# source_eagle.net
KiCad netlist of a schematic drawn in EAGLE
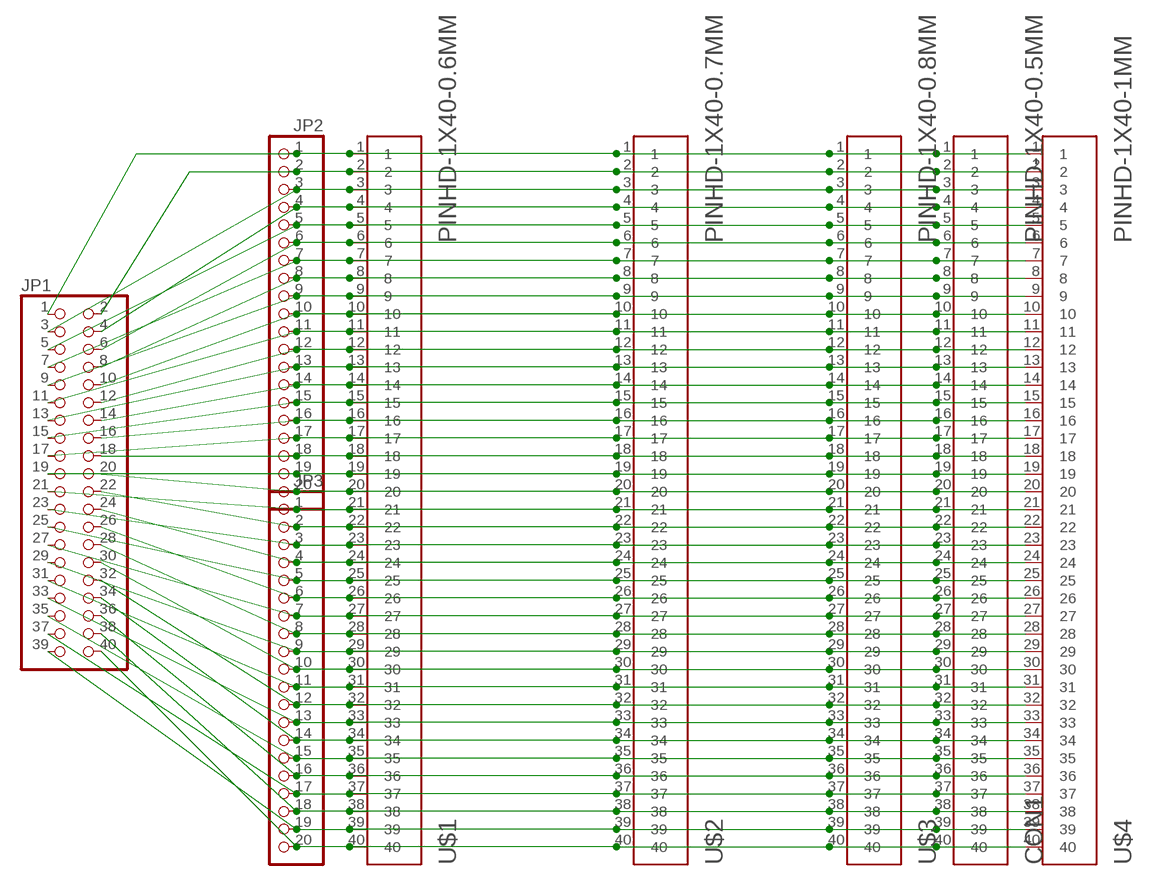
[diagram p0: schematic, sheet 1]

(export (version "E")
  (design (tool "Eeschema 10.0.6"))
  (components
    (comp (ref "CON1")
      (value "PINHD-1X40-0.5MM")
      (footprint "eagle-import:1X40-0.5MM")
      (libsource (lib "eagle-import") (part "PINHD-1X40-0.5MM"))
    )
    (comp (ref "JP1")
      (value "PINHD-2X20-BIG")
      (footprint "eagle-import:2X20-BIG")
      (libsource (lib "eagle-import") (part "PINHD-2X20-BIG"))
    )
    (comp (ref "JP2")
      (value "PINHD-1X20-BIG")
      (footprint "eagle-import:1X20-BIG")
      (libsource (lib "eagle-import") (part "PINHD-1X20-BIG"))
    )
    (comp (ref "JP3")
      (value "PINHD-1X20-BIG")
      (footprint "eagle-import:1X20-BIG")
      (libsource (lib "eagle-import") (part "PINHD-1X20-BIG"))
    )
    (comp (ref "U$1")
      (value "PINHD-1X40-0.6MM")
      (footprint "eagle-import:1X40-0.6MM")
      (libsource (lib "eagle-import") (part "PINHD-1X40-0.6MM"))
    )
    (comp (ref "U$2")
      (value "PINHD-1X40-0.7MM")
      (footprint "eagle-import:1X40-0.7MM")
      (libsource (lib "eagle-import") (part "PINHD-1X40-0.7MM"))
    )
    (comp (ref "U$3")
      (value "PINHD-1X40-0.8MM")
      (footprint "eagle-import:1X40-0.8MM")
      (libsource (lib "eagle-import") (part "PINHD-1X40-0.8MM"))
    )
    (comp (ref "U$4")
      (value "PINHD-1X40-1MM")
      (footprint "eagle-import:1X40-1MM")
      (libsource (lib "eagle-import") (part "PINHD-1X40-1MM"))
    )
  )
  (nets
    (net (code "1") (name "Net-(CON1-Pad1)") (class "Default")
      (node (ref "CON1") (pin "1") (pinfunction "1_1") (pintype "bidirectional"))
      (node (ref "JP1") (pin "1") (pinfunction "1_1") (pintype "passive"))
      (node (ref "JP2") (pin "1") (pinfunction "1_1") (pintype "passive"))
      (node (ref "U$1") (pin "1") (pinfunction "1_1") (pintype "bidirectional"))
      (node (ref "U$2") (pin "1") (pinfunction "1_1") (pintype "bidirectional"))
      (node (ref "U$3") (pin "1") (pinfunction "1_1") (pintype "bidirectional"))
      (node (ref "U$4") (pin "1") (pinfunction "1_1") (pintype "bidirectional"))
    )
    (net (code "2") (name "Net-(CON1-Pad2)") (class "Default")
      (node (ref "CON1") (pin "2") (pinfunction "2_2") (pintype "bidirectional"))
      (node (ref "JP1") (pin "2") (pinfunction "2_2") (pintype "passive"))
      (node (ref "JP2") (pin "2") (pinfunction "2_2") (pintype "passive"))
      (node (ref "U$1") (pin "2") (pinfunction "2_2") (pintype "bidirectional"))
      (node (ref "U$2") (pin "2") (pinfunction "2_2") (pintype "bidirectional"))
      (node (ref "U$3") (pin "2") (pinfunction "2_2") (pintype "bidirectional"))
      (node (ref "U$4") (pin "2") (pinfunction "2_2") (pintype "bidirectional"))
    )
    (net (code "3") (name "Net-(CON1-Pad3)") (class "Default")
      (node (ref "CON1") (pin "3") (pinfunction "3_3") (pintype "bidirectional"))
      (node (ref "JP1") (pin "3") (pinfunction "3_3") (pintype "passive"))
      (node (ref "JP2") (pin "3") (pinfunction "3_3") (pintype "passive"))
      (node (ref "U$1") (pin "3") (pinfunction "3_3") (pintype "bidirectional"))
      (node (ref "U$2") (pin "3") (pinfunction "3_3") (pintype "bidirectional"))
      (node (ref "U$3") (pin "3") (pinfunction "3_3") (pintype "bidirectional"))
      (node (ref "U$4") (pin "3") (pinfunction "3_3") (pintype "bidirectional"))
    )
    (net (code "4") (name "Net-(CON1-Pad4)") (class "Default")
      (node (ref "CON1") (pin "4") (pinfunction "4_4") (pintype "bidirectional"))
      (node (ref "JP1") (pin "4") (pinfunction "4_4") (pintype "passive"))
      (node (ref "JP2") (pin "4") (pinfunction "4_4") (pintype "passive"))
      (node (ref "U$1") (pin "4") (pinfunction "4_4") (pintype "bidirectional"))
      (node (ref "U$2") (pin "4") (pinfunction "4_4") (pintype "bidirectional"))
      (node (ref "U$3") (pin "4") (pinfunction "4_4") (pintype "bidirectional"))
      (node (ref "U$4") (pin "4") (pinfunction "4_4") (pintype "bidirectional"))
    )
    (net (code "5") (name "Net-(CON1-Pad5)") (class "Default")
      (node (ref "CON1") (pin "5") (pinfunction "5_5") (pintype "bidirectional"))
      (node (ref "JP1") (pin "5") (pinfunction "5_5") (pintype "passive"))
      (node (ref "JP2") (pin "5") (pinfunction "5_5") (pintype "passive"))
      (node (ref "U$1") (pin "5") (pinfunction "5_5") (pintype "bidirectional"))
      (node (ref "U$2") (pin "5") (pinfunction "5_5") (pintype "bidirectional"))
      (node (ref "U$3") (pin "5") (pinfunction "5_5") (pintype "bidirectional"))
      (node (ref "U$4") (pin "5") (pinfunction "5_5") (pintype "bidirectional"))
    )
    (net (code "6") (name "Net-(CON1-Pad6)") (class "Default")
      (node (ref "CON1") (pin "6") (pinfunction "6_6") (pintype "bidirectional"))
      (node (ref "JP1") (pin "6") (pinfunction "6_6") (pintype "passive"))
      (node (ref "JP2") (pin "6") (pinfunction "6_6") (pintype "passive"))
      (node (ref "U$1") (pin "6") (pinfunction "6_6") (pintype "bidirectional"))
      (node (ref "U$2") (pin "6") (pinfunction "6_6") (pintype "bidirectional"))
      (node (ref "U$3") (pin "6") (pinfunction "6_6") (pintype "bidirectional"))
      (node (ref "U$4") (pin "6") (pinfunction "6_6") (pintype "bidirectional"))
    )
    (net (code "7") (name "Net-(CON1-Pad7)") (class "Default")
      (node (ref "CON1") (pin "7") (pinfunction "7_7") (pintype "bidirectional"))
      (node (ref "JP1") (pin "7") (pinfunction "7_7") (pintype "passive"))
      (node (ref "JP2") (pin "7") (pinfunction "7_7") (pintype "passive"))
      (node (ref "U$1") (pin "7") (pinfunction "7_7") (pintype "bidirectional"))
      (node (ref "U$2") (pin "7") (pinfunction "7_7") (pintype "bidirectional"))
      (node (ref "U$3") (pin "7") (pinfunction "7_7") (pintype "bidirectional"))
      (node (ref "U$4") (pin "7") (pinfunction "7_7") (pintype "bidirectional"))
    )
    (net (code "8") (name "Net-(CON1-Pad8)") (class "Default")
      (node (ref "CON1") (pin "8") (pinfunction "8_8") (pintype "bidirectional"))
      (node (ref "JP1") (pin "8") (pinfunction "8_8") (pintype "passive"))
      (node (ref "JP2") (pin "8") (pinfunction "8_8") (pintype "passive"))
      (node (ref "U$1") (pin "8") (pinfunction "8_8") (pintype "bidirectional"))
      (node (ref "U$2") (pin "8") (pinfunction "8_8") (pintype "bidirectional"))
      (node (ref "U$3") (pin "8") (pinfunction "8_8") (pintype "bidirectional"))
      (node (ref "U$4") (pin "8") (pinfunction "8_8") (pintype "bidirectional"))
    )
    (net (code "9") (name "Net-(CON1-Pad9)") (class "Default")
      (node (ref "CON1") (pin "9") (pinfunction "9_9") (pintype "bidirectional"))
      (node (ref "JP1") (pin "9") (pinfunction "9_9") (pintype "passive"))
      (node (ref "JP2") (pin "9") (pinfunction "9_9") (pintype "passive"))
      (node (ref "U$1") (pin "9") (pinfunction "9_9") (pintype "bidirectional"))
      (node (ref "U$2") (pin "9") (pinfunction "9_9") (pintype "bidirectional"))
      (node (ref "U$3") (pin "9") (pinfunction "9_9") (pintype "bidirectional"))
      (node (ref "U$4") (pin "9") (pinfunction "9_9") (pintype "bidirectional"))
    )
    (net (code "10") (name "Net-(CON1-Pad10)") (class "Default")
      (node (ref "CON1") (pin "10") (pinfunction "10_10") (pintype "bidirectional"))
      (node (ref "JP1") (pin "10") (pinfunction "10_10") (pintype "passive"))
      (node (ref "JP2") (pin "10") (pinfunction "10_10") (pintype "passive"))
      (node (ref "U$1") (pin "10") (pinfunction "10_10") (pintype "bidirectional"))
      (node (ref "U$2") (pin "10") (pinfunction "10_10") (pintype "bidirectional"))
      (node (ref "U$3") (pin "10") (pinfunction "10_10") (pintype "bidirectional"))
      (node (ref "U$4") (pin "10") (pinfunction "10_10") (pintype "bidirectional"))
    )
    (net (code "11") (name "Net-(CON1-Pad11)") (class "Default")
      (node (ref "CON1") (pin "11") (pinfunction "11_11") (pintype "bidirectional"))
      (node (ref "JP1") (pin "11") (pinfunction "11_11") (pintype "passive"))
      (node (ref "JP2") (pin "11") (pinfunction "11_11") (pintype "passive"))
      (node (ref "U$1") (pin "11") (pinfunction "11_11") (pintype "bidirectional"))
      (node (ref "U$2") (pin "11") (pinfunction "11_11") (pintype "bidirectional"))
      (node (ref "U$3") (pin "11") (pinfunction "11_11") (pintype "bidirectional"))
      (node (ref "U$4") (pin "11") (pinfunction "11_11") (pintype "bidirectional"))
    )
    (net (code "12") (name "Net-(CON1-Pad12)") (class "Default")
      (node (ref "CON1") (pin "12") (pinfunction "12_12") (pintype "bidirectional"))
      (node (ref "JP1") (pin "12") (pinfunction "12_12") (pintype "passive"))
      (node (ref "JP2") (pin "12") (pinfunction "12_12") (pintype "passive"))
      (node (ref "U$1") (pin "12") (pinfunction "12_12") (pintype "bidirectional"))
      (node (ref "U$2") (pin "12") (pinfunction "12_12") (pintype "bidirectional"))
      (node (ref "U$3") (pin "12") (pinfunction "12_12") (pintype "bidirectional"))
      (node (ref "U$4") (pin "12") (pinfunction "12_12") (pintype "bidirectional"))
    )
    (net (code "13") (name "Net-(CON1-Pad13)") (class "Default")
      (node (ref "CON1") (pin "13") (pinfunction "13_13") (pintype "bidirectional"))
      (node (ref "JP1") (pin "13") (pinfunction "13_13") (pintype "passive"))
      (node (ref "JP2") (pin "13") (pinfunction "13_13") (pintype "passive"))
      (node (ref "U$1") (pin "13") (pinfunction "13_13") (pintype "bidirectional"))
      (node (ref "U$2") (pin "13") (pinfunction "13_13") (pintype "bidirectional"))
      (node (ref "U$3") (pin "13") (pinfunction "13_13") (pintype "bidirectional"))
      (node (ref "U$4") (pin "13") (pinfunction "13_13") (pintype "bidirectional"))
    )
    (net (code "14") (name "Net-(CON1-Pad14)") (class "Default")
      (node (ref "CON1") (pin "14") (pinfunction "14_14") (pintype "bidirectional"))
      (node (ref "JP1") (pin "14") (pinfunction "14_14") (pintype "passive"))
      (node (ref "JP2") (pin "14") (pinfunction "14_14") (pintype "passive"))
      (node (ref "U$1") (pin "14") (pinfunction "14_14") (pintype "bidirectional"))
      (node (ref "U$2") (pin "14") (pinfunction "14_14") (pintype "bidirectional"))
      (node (ref "U$3") (pin "14") (pinfunction "14_14") (pintype "bidirectional"))
      (node (ref "U$4") (pin "14") (pinfunction "14_14") (pintype "bidirectional"))
    )
    (net (code "15") (name "Net-(CON1-Pad15)") (class "Default")
      (node (ref "CON1") (pin "15") (pinfunction "15_15") (pintype "bidirectional"))
      (node (ref "JP1") (pin "15") (pinfunction "15_15") (pintype "passive"))
      (node (ref "JP2") (pin "15") (pinfunction "15_15") (pintype "passive"))
      (node (ref "U$1") (pin "15") (pinfunction "15_15") (pintype "bidirectional"))
      (node (ref "U$2") (pin "15") (pinfunction "15_15") (pintype "bidirectional"))
      (node (ref "U$3") (pin "15") (pinfunction "15_15") (pintype "bidirectional"))
      (node (ref "U$4") (pin "15") (pinfunction "15_15") (pintype "bidirectional"))
    )
    (net (code "16") (name "Net-(CON1-Pad16)") (class "Default")
      (node (ref "CON1") (pin "16") (pinfunction "16_16") (pintype "bidirectional"))
      (node (ref "JP1") (pin "16") (pinfunction "16_16") (pintype "passive"))
      (node (ref "JP2") (pin "16") (pinfunction "16_16") (pintype "passive"))
      (node (ref "U$1") (pin "16") (pinfunction "16_16") (pintype "bidirectional"))
      (node (ref "U$2") (pin "16") (pinfunction "16_16") (pintype "bidirectional"))
      (node (ref "U$3") (pin "16") (pinfunction "16_16") (pintype "bidirectional"))
      (node (ref "U$4") (pin "16") (pinfunction "16_16") (pintype "bidirectional"))
    )
    (net (code "17") (name "Net-(CON1-Pad17)") (class "Default")
      (node (ref "CON1") (pin "17") (pinfunction "17_17") (pintype "bidirectional"))
      (node (ref "JP1") (pin "17") (pinfunction "17_17") (pintype "passive"))
      (node (ref "JP2") (pin "17") (pinfunction "17_17") (pintype "passive"))
      (node (ref "U$1") (pin "17") (pinfunction "17_17") (pintype "bidirectional"))
      (node (ref "U$2") (pin "17") (pinfunction "17_17") (pintype "bidirectional"))
      (node (ref "U$3") (pin "17") (pinfunction "17_17") (pintype "bidirectional"))
      (node (ref "U$4") (pin "17") (pinfunction "17_17") (pintype "bidirectional"))
    )
    (net (code "18") (name "Net-(CON1-Pad18)") (class "Default")
      (node (ref "CON1") (pin "18") (pinfunction "18_18") (pintype "bidirectional"))
      (node (ref "JP1") (pin "18") (pinfunction "18_18") (pintype "passive"))
      (node (ref "JP2") (pin "18") (pinfunction "18_18") (pintype "passive"))
      (node (ref "U$1") (pin "18") (pinfunction "18_18") (pintype "bidirectional"))
      (node (ref "U$2") (pin "18") (pinfunction "18_18") (pintype "bidirectional"))
      (node (ref "U$3") (pin "18") (pinfunction "18_18") (pintype "bidirectional"))
      (node (ref "U$4") (pin "18") (pinfunction "18_18") (pintype "bidirectional"))
    )
    (net (code "19") (name "Net-(CON1-Pad19)") (class "Default")
      (node (ref "CON1") (pin "19") (pinfunction "19_19") (pintype "bidirectional"))
      (node (ref "JP1") (pin "19") (pinfunction "19_19") (pintype "passive"))
      (node (ref "JP2") (pin "19") (pinfunction "19_19") (pintype "passive"))
      (node (ref "U$1") (pin "19") (pinfunction "19_19") (pintype "bidirectional"))
      (node (ref "U$2") (pin "19") (pinfunction "19_19") (pintype "bidirectional"))
      (node (ref "U$3") (pin "19") (pinfunction "19_19") (pintype "bidirectional"))
      (node (ref "U$4") (pin "19") (pinfunction "19_19") (pintype "bidirectional"))
    )
    (net (code "20") (name "Net-(CON1-Pad20)") (class "Default")
      (node (ref "CON1") (pin "20") (pinfunction "20_20") (pintype "bidirectional"))
      (node (ref "JP1") (pin "20") (pinfunction "20_20") (pintype "passive"))
      (node (ref "JP2") (pin "20") (pinfunction "20_20") (pintype "passive"))
      (node (ref "U$1") (pin "20") (pinfunction "20_20") (pintype "bidirectional"))
      (node (ref "U$2") (pin "20") (pinfunction "20_20") (pintype "bidirectional"))
      (node (ref "U$3") (pin "20") (pinfunction "20_20") (pintype "bidirectional"))
      (node (ref "U$4") (pin "20") (pinfunction "20_20") (pintype "bidirectional"))
    )
    (net (code "21") (name "Net-(CON1-Pad21)") (class "Default")
      (node (ref "CON1") (pin "21") (pinfunction "21_21") (pintype "bidirectional"))
      (node (ref "JP1") (pin "21") (pinfunction "21_21") (pintype "passive"))
      (node (ref "JP3") (pin "1") (pinfunction "1_1") (pintype "passive"))
      (node (ref "U$1") (pin "21") (pinfunction "21_21") (pintype "bidirectional"))
      (node (ref "U$2") (pin "21") (pinfunction "21_21") (pintype "bidirectional"))
      (node (ref "U$3") (pin "21") (pinfunction "21_21") (pintype "bidirectional"))
      (node (ref "U$4") (pin "21") (pinfunction "21_21") (pintype "bidirectional"))
    )
    (net (code "22") (name "Net-(CON1-Pad22)") (class "Default")
      (node (ref "CON1") (pin "22") (pinfunction "22_22") (pintype "bidirectional"))
      (node (ref "JP1") (pin "22") (pinfunction "22_22") (pintype "passive"))
      (node (ref "JP3") (pin "2") (pinfunction "2_2") (pintype "passive"))
      (node (ref "U$1") (pin "22") (pinfunction "22_22") (pintype "bidirectional"))
      (node (ref "U$2") (pin "22") (pinfunction "22_22") (pintype "bidirectional"))
      (node (ref "U$3") (pin "22") (pinfunction "22_22") (pintype "bidirectional"))
      (node (ref "U$4") (pin "22") (pinfunction "22_22") (pintype "bidirectional"))
    )
    (net (code "23") (name "Net-(CON1-Pad23)") (class "Default")
      (node (ref "CON1") (pin "23") (pinfunction "23_23") (pintype "bidirectional"))
      (node (ref "JP1") (pin "23") (pinfunction "23_23") (pintype "passive"))
      (node (ref "JP3") (pin "3") (pinfunction "3_3") (pintype "passive"))
      (node (ref "U$1") (pin "23") (pinfunction "23_23") (pintype "bidirectional"))
      (node (ref "U$2") (pin "23") (pinfunction "23_23") (pintype "bidirectional"))
      (node (ref "U$3") (pin "23") (pinfunction "23_23") (pintype "bidirectional"))
      (node (ref "U$4") (pin "23") (pinfunction "23_23") (pintype "bidirectional"))
    )
    (net (code "24") (name "Net-(CON1-Pad24)") (class "Default")
      (node (ref "CON1") (pin "24") (pinfunction "24_24") (pintype "bidirectional"))
      (node (ref "JP1") (pin "24") (pinfunction "24_24") (pintype "passive"))
      (node (ref "JP3") (pin "4") (pinfunction "4_4") (pintype "passive"))
      (node (ref "U$1") (pin "24") (pinfunction "24_24") (pintype "bidirectional"))
      (node (ref "U$2") (pin "24") (pinfunction "24_24") (pintype "bidirectional"))
      (node (ref "U$3") (pin "24") (pinfunction "24_24") (pintype "bidirectional"))
      (node (ref "U$4") (pin "24") (pinfunction "24_24") (pintype "bidirectional"))
    )
    (net (code "25") (name "Net-(CON1-Pad25)") (class "Default")
      (node (ref "CON1") (pin "25") (pinfunction "25_25") (pintype "bidirectional"))
      (node (ref "JP1") (pin "25") (pinfunction "25_25") (pintype "passive"))
      (node (ref "JP3") (pin "5") (pinfunction "5_5") (pintype "passive"))
      (node (ref "U$1") (pin "25") (pinfunction "25_25") (pintype "bidirectional"))
      (node (ref "U$2") (pin "25") (pinfunction "25_25") (pintype "bidirectional"))
      (node (ref "U$3") (pin "25") (pinfunction "25_25") (pintype "bidirectional"))
      (node (ref "U$4") (pin "25") (pinfunction "25_25") (pintype "bidirectional"))
    )
    (net (code "26") (name "Net-(CON1-Pad26)") (class "Default")
      (node (ref "CON1") (pin "26") (pinfunction "26_26") (pintype "bidirectional"))
      (node (ref "JP1") (pin "26") (pinfunction "26_26") (pintype "passive"))
      (node (ref "JP3") (pin "6") (pinfunction "6_6") (pintype "passive"))
      (node (ref "U$1") (pin "26") (pinfunction "26_26") (pintype "bidirectional"))
      (node (ref "U$2") (pin "26") (pinfunction "26_26") (pintype "bidirectional"))
      (node (ref "U$3") (pin "26") (pinfunction "26_26") (pintype "bidirectional"))
      (node (ref "U$4") (pin "26") (pinfunction "26_26") (pintype "bidirectional"))
    )
    (net (code "27") (name "Net-(CON1-Pad27)") (class "Default")
      (node (ref "CON1") (pin "27") (pinfunction "27_27") (pintype "bidirectional"))
      (node (ref "JP1") (pin "27") (pinfunction "27_27") (pintype "passive"))
      (node (ref "JP3") (pin "7") (pinfunction "7_7") (pintype "passive"))
      (node (ref "U$1") (pin "27") (pinfunction "27_27") (pintype "bidirectional"))
      (node (ref "U$2") (pin "27") (pinfunction "27_27") (pintype "bidirectional"))
      (node (ref "U$3") (pin "27") (pinfunction "27_27") (pintype "bidirectional"))
      (node (ref "U$4") (pin "27") (pinfunction "27_27") (pintype "bidirectional"))
    )
    (net (code "28") (name "Net-(CON1-Pad28)") (class "Default")
      (node (ref "CON1") (pin "28") (pinfunction "28_28") (pintype "bidirectional"))
      (node (ref "JP1") (pin "28") (pinfunction "28_28") (pintype "passive"))
      (node (ref "JP3") (pin "8") (pinfunction "8_8") (pintype "passive"))
      (node (ref "U$1") (pin "28") (pinfunction "28_28") (pintype "bidirectional"))
      (node (ref "U$2") (pin "28") (pinfunction "28_28") (pintype "bidirectional"))
      (node (ref "U$3") (pin "28") (pinfunction "28_28") (pintype "bidirectional"))
      (node (ref "U$4") (pin "28") (pinfunction "28_28") (pintype "bidirectional"))
    )
    (net (code "29") (name "Net-(CON1-Pad29)") (class "Default")
      (node (ref "CON1") (pin "29") (pinfunction "29_29") (pintype "bidirectional"))
      (node (ref "JP1") (pin "29") (pinfunction "29_29") (pintype "passive"))
      (node (ref "JP3") (pin "9") (pinfunction "9_9") (pintype "passive"))
      (node (ref "U$1") (pin "29") (pinfunction "29_29") (pintype "bidirectional"))
      (node (ref "U$2") (pin "29") (pinfunction "29_29") (pintype "bidirectional"))
      (node (ref "U$3") (pin "29") (pinfunction "29_29") (pintype "bidirectional"))
      (node (ref "U$4") (pin "29") (pinfunction "29_29") (pintype "bidirectional"))
    )
    (net (code "30") (name "Net-(CON1-Pad30)") (class "Default")
      (node (ref "CON1") (pin "30") (pinfunction "30_30") (pintype "bidirectional"))
      (node (ref "JP1") (pin "30") (pinfunction "30_30") (pintype "passive"))
      (node (ref "JP3") (pin "10") (pinfunction "10_10") (pintype "passive"))
      (node (ref "U$1") (pin "30") (pinfunction "30_30") (pintype "bidirectional"))
      (node (ref "U$2") (pin "30") (pinfunction "30_30") (pintype "bidirectional"))
      (node (ref "U$3") (pin "30") (pinfunction "30_30") (pintype "bidirectional"))
      (node (ref "U$4") (pin "30") (pinfunction "30_30") (pintype "bidirectional"))
    )
    (net (code "31") (name "Net-(CON1-Pad31)") (class "Default")
      (node (ref "CON1") (pin "31") (pinfunction "31_31") (pintype "bidirectional"))
      (node (ref "JP1") (pin "31") (pinfunction "31_31") (pintype "passive"))
      (node (ref "JP3") (pin "11") (pinfunction "11_11") (pintype "passive"))
      (node (ref "U$1") (pin "31") (pinfunction "31_31") (pintype "bidirectional"))
      (node (ref "U$2") (pin "31") (pinfunction "31_31") (pintype "bidirectional"))
      (node (ref "U$3") (pin "31") (pinfunction "31_31") (pintype "bidirectional"))
      (node (ref "U$4") (pin "31") (pinfunction "31_31") (pintype "bidirectional"))
    )
    (net (code "32") (name "Net-(CON1-Pad32)") (class "Default")
      (node (ref "CON1") (pin "32") (pinfunction "32_32") (pintype "bidirectional"))
      (node (ref "JP1") (pin "32") (pinfunction "32_32") (pintype "passive"))
      (node (ref "JP3") (pin "12") (pinfunction "12_12") (pintype "passive"))
      (node (ref "U$1") (pin "32") (pinfunction "32_32") (pintype "bidirectional"))
      (node (ref "U$2") (pin "32") (pinfunction "32_32") (pintype "bidirectional"))
      (node (ref "U$3") (pin "32") (pinfunction "32_32") (pintype "bidirectional"))
      (node (ref "U$4") (pin "32") (pinfunction "32_32") (pintype "bidirectional"))
    )
    (net (code "33") (name "Net-(CON1-Pad33)") (class "Default")
      (node (ref "CON1") (pin "33") (pinfunction "33_33") (pintype "bidirectional"))
      (node (ref "JP1") (pin "33") (pinfunction "33_33") (pintype "passive"))
      (node (ref "JP3") (pin "13") (pinfunction "13_13") (pintype "passive"))
      (node (ref "U$1") (pin "33") (pinfunction "33_33") (pintype "bidirectional"))
      (node (ref "U$2") (pin "33") (pinfunction "33_33") (pintype "bidirectional"))
      (node (ref "U$3") (pin "33") (pinfunction "33_33") (pintype "bidirectional"))
      (node (ref "U$4") (pin "33") (pinfunction "33_33") (pintype "bidirectional"))
    )
    (net (code "34") (name "Net-(CON1-Pad34)") (class "Default")
      (node (ref "CON1") (pin "34") (pinfunction "34_34") (pintype "bidirectional"))
      (node (ref "JP1") (pin "34") (pinfunction "34_34") (pintype "passive"))
      (node (ref "JP3") (pin "14") (pinfunction "14_14") (pintype "passive"))
      (node (ref "U$1") (pin "34") (pinfunction "34_34") (pintype "bidirectional"))
      (node (ref "U$2") (pin "34") (pinfunction "34_34") (pintype "bidirectional"))
      (node (ref "U$3") (pin "34") (pinfunction "34_34") (pintype "bidirectional"))
      (node (ref "U$4") (pin "34") (pinfunction "34_34") (pintype "bidirectional"))
    )
    (net (code "35") (name "Net-(CON1-Pad35)") (class "Default")
      (node (ref "CON1") (pin "35") (pinfunction "35_35") (pintype "bidirectional"))
      (node (ref "JP1") (pin "35") (pinfunction "35_35") (pintype "passive"))
      (node (ref "JP3") (pin "15") (pinfunction "15_15") (pintype "passive"))
      (node (ref "U$1") (pin "35") (pinfunction "35_35") (pintype "bidirectional"))
      (node (ref "U$2") (pin "35") (pinfunction "35_35") (pintype "bidirectional"))
      (node (ref "U$3") (pin "35") (pinfunction "35_35") (pintype "bidirectional"))
      (node (ref "U$4") (pin "35") (pinfunction "35_35") (pintype "bidirectional"))
    )
    (net (code "36") (name "Net-(CON1-Pad36)") (class "Default")
      (node (ref "CON1") (pin "36") (pinfunction "36_36") (pintype "bidirectional"))
      (node (ref "JP1") (pin "36") (pinfunction "36_36") (pintype "passive"))
      (node (ref "JP3") (pin "16") (pinfunction "16_16") (pintype "passive"))
      (node (ref "U$1") (pin "36") (pinfunction "36_36") (pintype "bidirectional"))
      (node (ref "U$2") (pin "36") (pinfunction "36_36") (pintype "bidirectional"))
      (node (ref "U$3") (pin "36") (pinfunction "36_36") (pintype "bidirectional"))
      (node (ref "U$4") (pin "36") (pinfunction "36_36") (pintype "bidirectional"))
    )
    (net (code "37") (name "Net-(CON1-Pad37)") (class "Default")
      (node (ref "CON1") (pin "37") (pinfunction "37_37") (pintype "bidirectional"))
      (node (ref "JP1") (pin "37") (pinfunction "37_37") (pintype "passive"))
      (node (ref "JP3") (pin "17") (pinfunction "17_17") (pintype "passive"))
      (node (ref "U$1") (pin "37") (pinfunction "37_37") (pintype "bidirectional"))
      (node (ref "U$2") (pin "37") (pinfunction "37_37") (pintype "bidirectional"))
      (node (ref "U$3") (pin "37") (pinfunction "37_37") (pintype "bidirectional"))
      (node (ref "U$4") (pin "37") (pinfunction "37_37") (pintype "bidirectional"))
    )
    (net (code "38") (name "Net-(CON1-Pad38)") (class "Default")
      (node (ref "CON1") (pin "38") (pinfunction "38_38") (pintype "bidirectional"))
      (node (ref "JP1") (pin "38") (pinfunction "38_38") (pintype "passive"))
      (node (ref "JP3") (pin "18") (pinfunction "18_18") (pintype "passive"))
      (node (ref "U$1") (pin "38") (pinfunction "38_38") (pintype "bidirectional"))
      (node (ref "U$2") (pin "38") (pinfunction "38_38") (pintype "bidirectional"))
      (node (ref "U$3") (pin "38") (pinfunction "38_38") (pintype "bidirectional"))
      (node (ref "U$4") (pin "38") (pinfunction "38_38") (pintype "bidirectional"))
    )
    (net (code "39") (name "Net-(CON1-Pad39)") (class "Default")
      (node (ref "CON1") (pin "39") (pinfunction "39_39") (pintype "bidirectional"))
      (node (ref "JP1") (pin "39") (pinfunction "39_39") (pintype "passive"))
      (node (ref "JP3") (pin "19") (pinfunction "19_19") (pintype "passive"))
      (node (ref "U$1") (pin "39") (pinfunction "39_39") (pintype "bidirectional"))
      (node (ref "U$2") (pin "39") (pinfunction "39_39") (pintype "bidirectional"))
      (node (ref "U$3") (pin "39") (pinfunction "39_39") (pintype "bidirectional"))
      (node (ref "U$4") (pin "39") (pinfunction "39_39") (pintype "bidirectional"))
    )
    (net (code "40") (name "Net-(CON1-Pad40)") (class "Default")
      (node (ref "CON1") (pin "40") (pinfunction "40_40") (pintype "bidirectional"))
      (node (ref "JP1") (pin "40") (pinfunction "40_40") (pintype "passive"))
      (node (ref "JP3") (pin "20") (pinfunction "20_20") (pintype "passive"))
      (node (ref "U$1") (pin "40") (pinfunction "40_40") (pintype "bidirectional"))
      (node (ref "U$2") (pin "40") (pinfunction "40_40") (pintype "bidirectional"))
      (node (ref "U$3") (pin "40") (pinfunction "40_40") (pintype "bidirectional"))
      (node (ref "U$4") (pin "40") (pinfunction "40_40") (pintype "bidirectional"))
    )
  )
)
